# Rectifier_Unit.net
KiCad netlist of a schematic drawn in Altium Designer
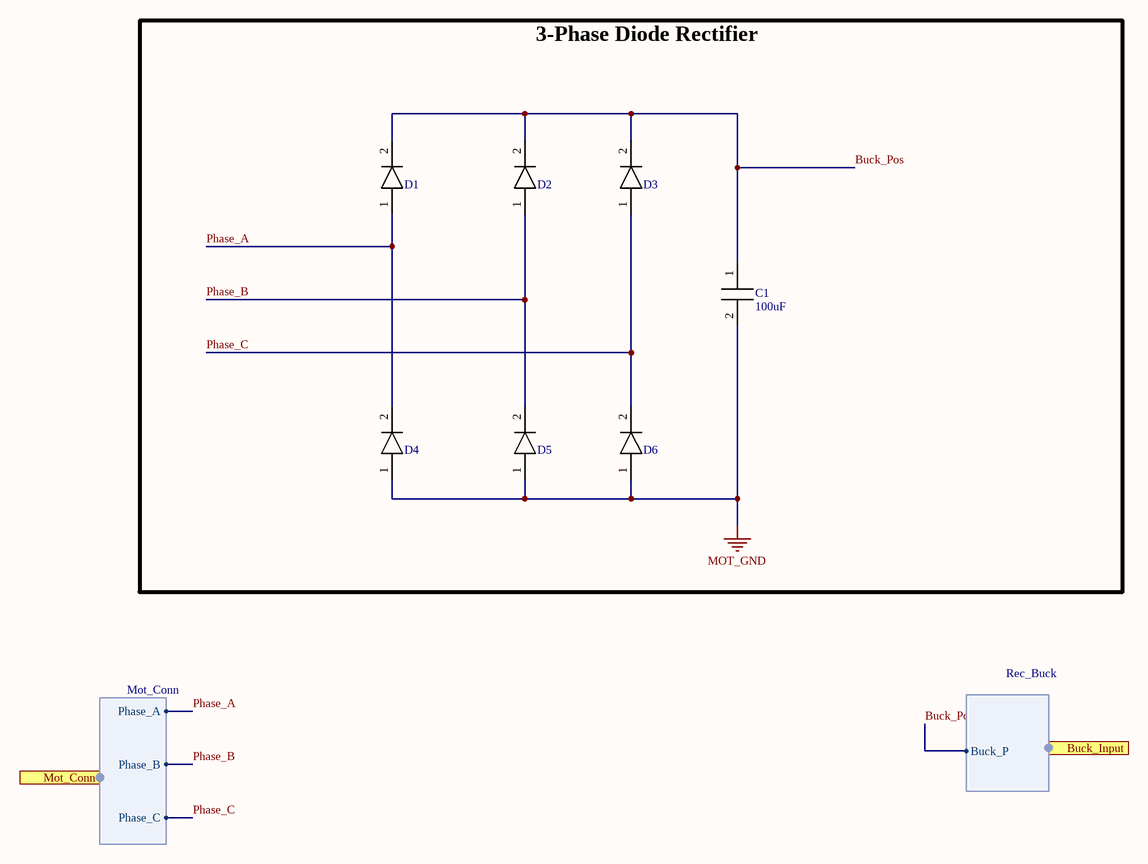
[diagram p0: Rectifier_Unit.SchDoc]

(export (version "E")
  (design (tool "Eeschema 10.0.6"))
  (components
    (comp (ref "C1")
      (value "CAP 100uf EKXL401ELL101MM25S")
      (footprint "EKXL401ELL101MM25S")
      (fields (field (name "PARAMETER 1") "100uF"))
      (libsource (lib "Schlib1") (part "CAP 100uf EKXL401ELL101MM25S"))
    )
    (comp (ref "D1")
      (value "DI S2GTR")
      (footprint "S2GTR")
      (description "DI, S2GTR, 400V, 2A")
      (libsource (lib "Schlib1") (part "DI S2GTR"))
    )
    (comp (ref "D2")
      (value "DI S2GTR")
      (footprint "S2GTR")
      (description "DI, S2GTR, 400V, 2A")
      (libsource (lib "Schlib1") (part "DI S2GTR"))
    )
    (comp (ref "D3")
      (value "DI S2GTR")
      (footprint "S2GTR")
      (description "DI, S2GTR, 400V, 2A")
      (libsource (lib "Schlib1") (part "DI S2GTR"))
    )
    (comp (ref "D4")
      (value "DI S2GTR")
      (footprint "S2GTR")
      (description "DI, S2GTR, 400V, 2A")
      (libsource (lib "Schlib1") (part "DI S2GTR"))
    )
    (comp (ref "D5")
      (value "DI S2GTR")
      (footprint "S2GTR")
      (description "DI, S2GTR, 400V, 2A")
      (libsource (lib "Schlib1") (part "DI S2GTR"))
    )
    (comp (ref "D6")
      (value "DI S2GTR")
      (footprint "S2GTR")
      (description "DI, S2GTR, 400V, 2A")
      (libsource (lib "Schlib1") (part "DI S2GTR"))
    )
  )
  (nets
    (net (code "3") (name "/Buck_Pos") (class "Default")
      (node (ref "C1") (pin "1") (pinfunction "1_1") (pintype "passive"))
      (node (ref "D1") (pin "2") (pinfunction "Cathode_2") (pintype "passive"))
      (node (ref "D2") (pin "2") (pinfunction "Cathode_2") (pintype "passive"))
      (node (ref "D3") (pin "2") (pinfunction "Cathode_2") (pintype "passive"))
    )
    (net (code "4") (name "/Phase_A") (class "Default")
      (node (ref "D1") (pin "1") (pinfunction "Anode_1") (pintype "passive"))
      (node (ref "D4") (pin "2") (pinfunction "Cathode_2") (pintype "passive"))
    )
    (net (code "5") (name "/Phase_B") (class "Default")
      (node (ref "D2") (pin "1") (pinfunction "Anode_1") (pintype "passive"))
      (node (ref "D5") (pin "2") (pinfunction "Cathode_2") (pintype "passive"))
    )
    (net (code "6") (name "/Phase_C") (class "Default")
      (node (ref "D3") (pin "1") (pinfunction "Anode_1") (pintype "passive"))
      (node (ref "D6") (pin "2") (pinfunction "Cathode_2") (pintype "passive"))
    )
    (net (code "9") (name "MOT_GND") (class "Default")
      (node (ref "C1") (pin "2") (pinfunction "2_2") (pintype "passive"))
      (node (ref "D4") (pin "1") (pinfunction "Anode_1") (pintype "passive"))
      (node (ref "D5") (pin "1") (pinfunction "Anode_1") (pintype "passive"))
      (node (ref "D6") (pin "1") (pinfunction "Anode_1") (pintype "passive"))
    )
  )
)
